# design.net
KiCad netlist of a schematic drawn in Altium Designer
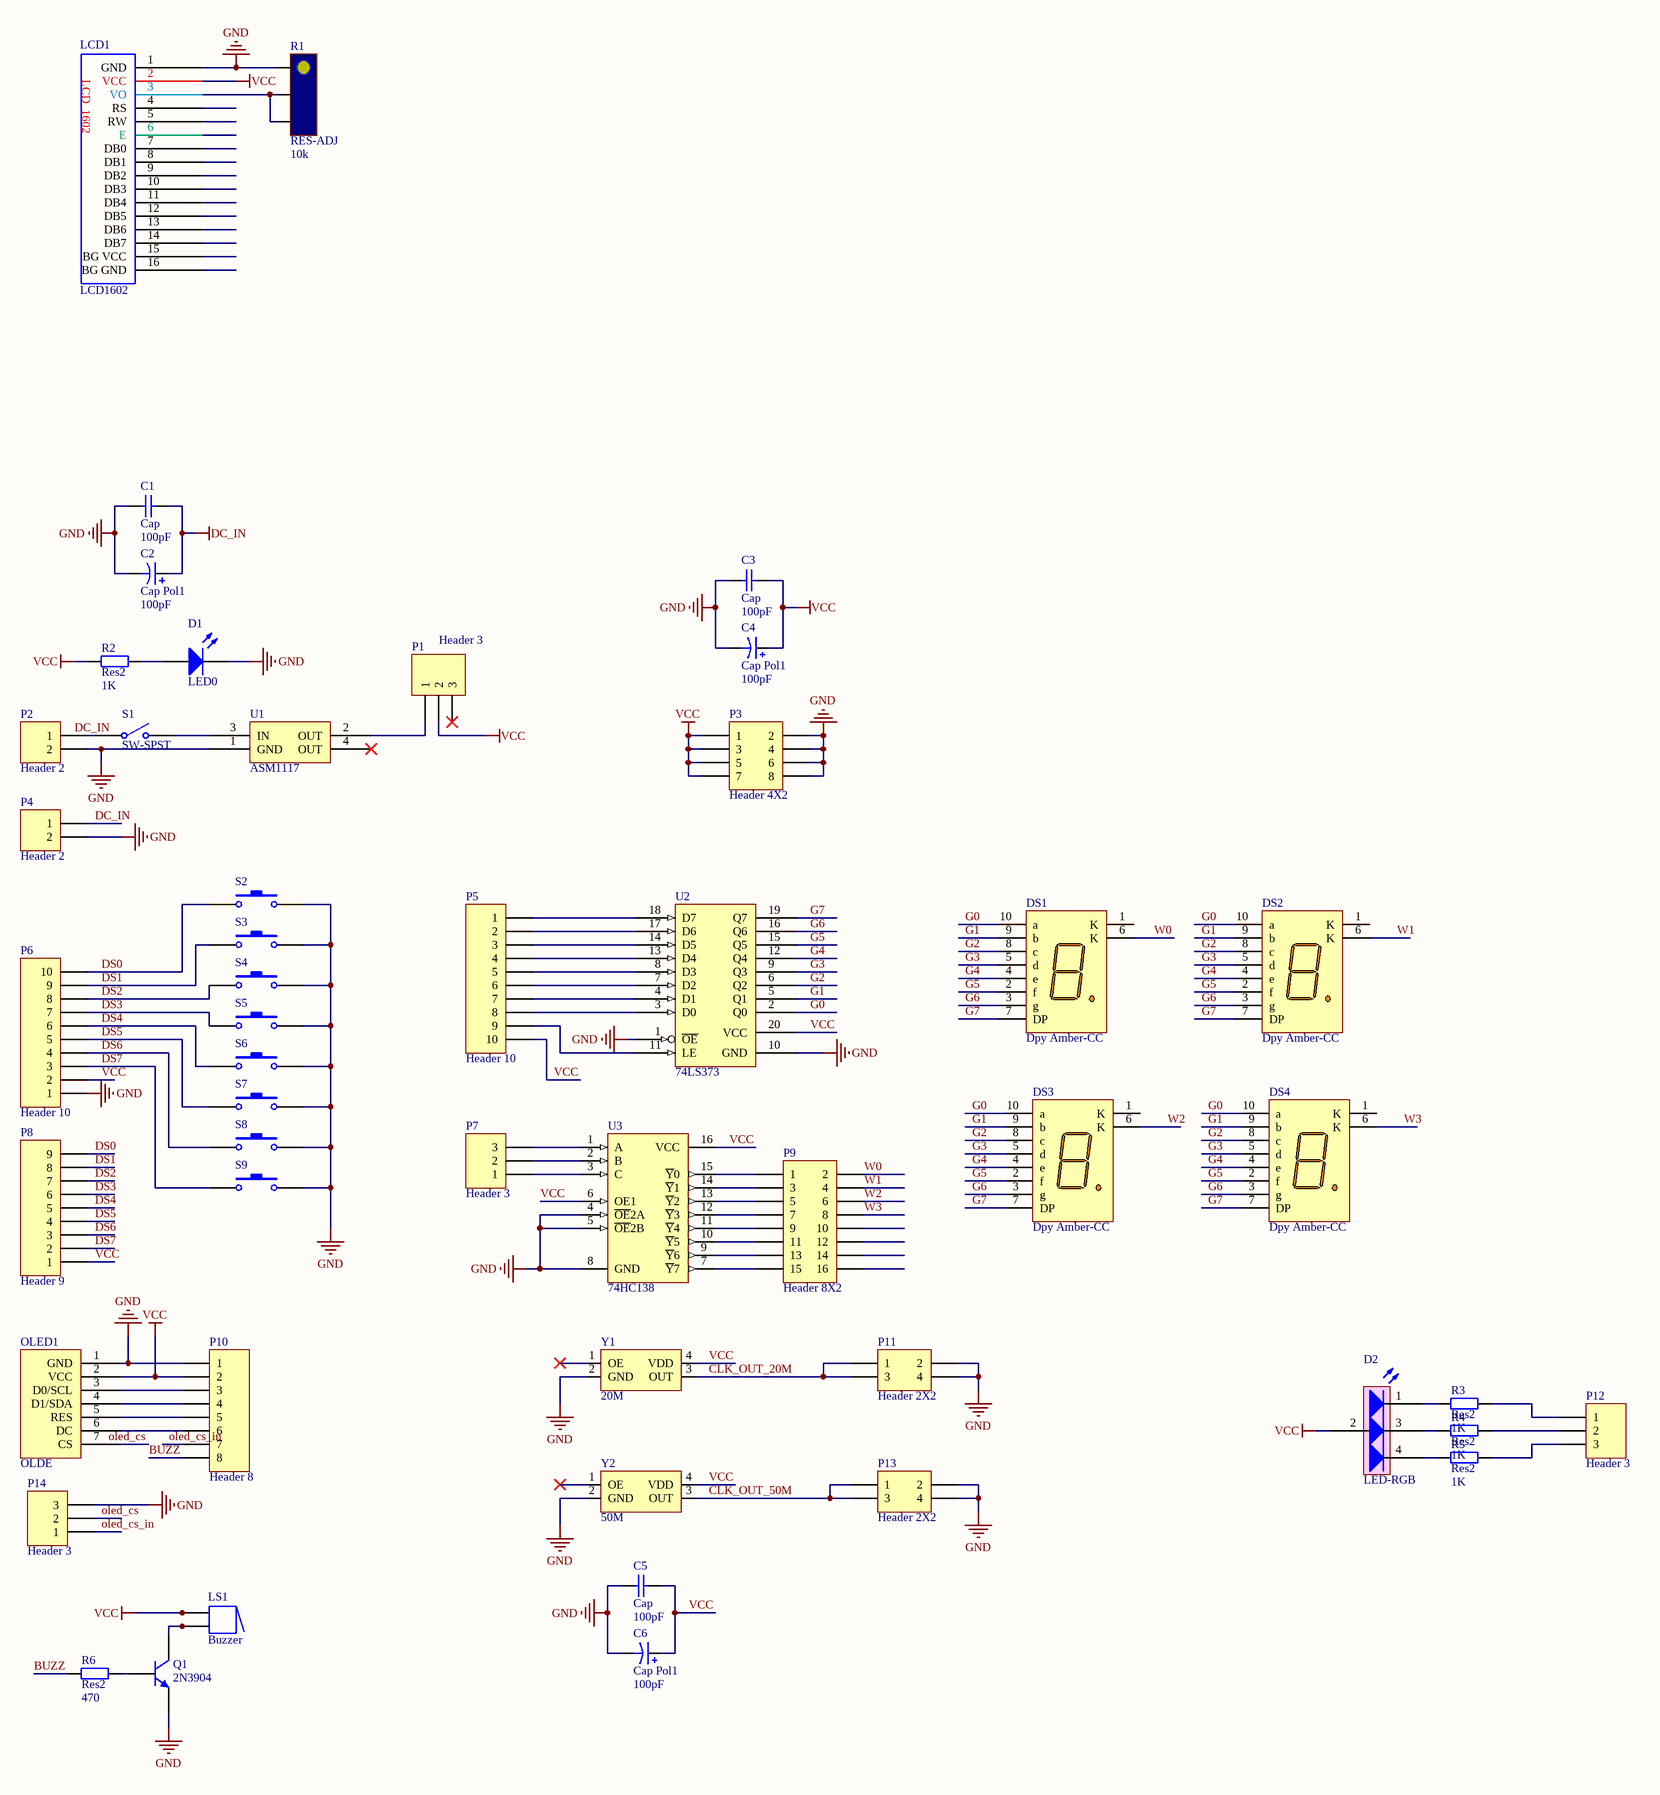
[diagram p0: 按键_数码管.SchDoc]

(export (version "E")
  (design (tool "Eeschema 10.0.6"))
  (components
    (comp (ref "C1")
      (value "Cap")
      (footprint "C-0805")
      (description "Capacitor")
      (fields (field (name "ALTIUM_VALUE") "100pF") (field (name "PUBLISHER") "Altium Limited"))
      (libsource (lib "Miscellaneous Devices") (part "Cap"))
    )
    (comp (ref "C2")
      (value "Cap Pol1")
      (footprint "C-RB-8")
      (description "Polarized Capacitor (Radial)")
      (fields (field (name "ALTIUM_VALUE") "100pF") (field (name "PUBLISHER") "Altium Limited"))
      (libsource (lib "Miscellaneous Devices") (part "Cap Pol1"))
    )
    (comp (ref "C3")
      (value "Cap")
      (footprint "C-0805")
      (description "Capacitor")
      (fields (field (name "ALTIUM_VALUE") "100pF") (field (name "PUBLISHER") "Altium Limited"))
      (libsource (lib "Miscellaneous Devices") (part "Cap"))
    )
    (comp (ref "C4")
      (value "Cap Pol1")
      (footprint "C-RB-8")
      (description "Polarized Capacitor (Radial)")
      (fields (field (name "ALTIUM_VALUE") "100pF") (field (name "PUBLISHER") "Altium Limited"))
      (libsource (lib "Miscellaneous Devices") (part "Cap Pol1"))
    )
    (comp (ref "C5")
      (value "Cap")
      (footprint "C-0805")
      (description "Capacitor")
      (fields (field (name "ALTIUM_VALUE") "100pF") (field (name "PUBLISHER") "Altium Limited"))
      (libsource (lib "Miscellaneous Devices") (part "Cap"))
    )
    (comp (ref "C6")
      (value "Cap Pol1")
      (footprint "C-RB-8")
      (description "Polarized Capacitor (Radial)")
      (fields (field (name "ALTIUM_VALUE") "100pF") (field (name "PUBLISHER") "Altium Limited"))
      (libsource (lib "Miscellaneous Devices") (part "Cap Pol1"))
    )
    (comp (ref "D1")
      (value "LED0")
      (footprint "LED")
      (description "Typical INFRARED GaAs LED")
      (fields (field (name "PUBLISHER") "Altium Limited"))
      (libsource (lib "Miscellaneous Devices") (part "LED0"))
    )
    (comp (ref "D2")
      (value "LED-RGB")
      (footprint "LED-RGB")
      (description "三基色LED")
      (fields (field (name "PUBLISHER") "Altium Limited"))
      (libsource (lib "常用封装") (part "LED-RGB"))
    )
    (comp (ref "DS1")
      (value "Dpy Amber-CC")
      (footprint "A")
      (description "7.62 mm Black Surface Orange 7-Segment Display: CC, RH DP")
      (fields (field (name "PUBLISHER") "Altium Limited"))
      (libsource (lib "Miscellaneous Devices") (part "Dpy Amber-CC"))
    )
    (comp (ref "DS2")
      (value "Dpy Amber-CC")
      (footprint "A")
      (description "7.62 mm Black Surface Orange 7-Segment Display: CC, RH DP")
      (fields (field (name "PUBLISHER") "Altium Limited"))
      (libsource (lib "Miscellaneous Devices") (part "Dpy Amber-CC"))
    )
    (comp (ref "DS3")
      (value "Dpy Amber-CC")
      (footprint "A")
      (description "7.62 mm Black Surface Orange 7-Segment Display: CC, RH DP")
      (fields (field (name "PUBLISHER") "Altium Limited"))
      (libsource (lib "Miscellaneous Devices") (part "Dpy Amber-CC"))
    )
    (comp (ref "DS4")
      (value "Dpy Amber-CC")
      (footprint "A")
      (description "7.62 mm Black Surface Orange 7-Segment Display: CC, RH DP")
      (fields (field (name "PUBLISHER") "Altium Limited"))
      (libsource (lib "Miscellaneous Devices") (part "Dpy Amber-CC"))
    )
    (comp (ref "LCD1") (value "LCD1602") (footprint "1602LCD") (libsource (lib "常用封装") (part "LCD1602")))
    (comp (ref "LS1")
      (value "Buzzer")
      (footprint "Beep")
      (description "Magnetic Transducer Buzzer")
      (fields (field (name "PUBLISHER") "Altium Limited"))
      (libsource (lib "Miscellaneous Devices") (part "Buzzer"))
    )
    (comp (ref "OLED1") (value "OLDE") (footprint "HDR1X7") (libsource (lib "常用封装") (part "OLED-0.96寸")))
    (comp (ref "P1")
      (value "Header 3")
      (footprint "HDR1X3")
      (description "Header, 3-Pin")
      (fields (field (name "PUBLISHER") "Altium Limited"))
      (libsource (lib "") (part "Header 3_1"))
    )
    (comp (ref "P2")
      (value "Header 2")
      (footprint "USB_B1")
      (description "Header, 2-Pin")
      (fields (field (name "PUBLISHER") "Altium Limited"))
      (libsource (lib "Miscellaneous Connectors") (part "Header 2"))
    )
    (comp (ref "P3")
      (value "Header 4X2")
      (footprint "HDR2X4")
      (description "Header, 4-Pin, Dual row")
      (fields (field (name "PUBLISHER") "Altium Limited"))
      (libsource (lib "Miscellaneous Connectors") (part "Header 4X2"))
    )
    (comp (ref "P4")
      (value "Header 2")
      (footprint "USB_B1")
      (description "Header, 2-Pin")
      (fields (field (name "PUBLISHER") "Altium Limited"))
      (libsource (lib "Miscellaneous Connectors") (part "Header 2"))
    )
    (comp (ref "P5")
      (value "Header 10")
      (footprint "HDR1X10")
      (description "Header, 10-Pin")
      (fields (field (name "PUBLISHER") "Altium Limited"))
      (libsource (lib "") (part "Header 10_1"))
    )
    (comp (ref "P6")
      (value "Header 10")
      (footprint "HDR1X10")
      (description "Header, 10-Pin")
      (fields (field (name "PUBLISHER") "Altium Limited"))
      (libsource (lib "Miscellaneous Connectors") (part "Header 10"))
    )
    (comp (ref "P7")
      (value "Header 3")
      (footprint "HDR1X3")
      (description "Header, 3-Pin")
      (fields (field (name "PUBLISHER") "Altium Limited"))
      (libsource (lib "") (part "Header 3_2"))
    )
    (comp (ref "P8")
      (value "Header 9")
      (footprint "HDR1X9")
      (description "Header, 9-Pin")
      (fields (field (name "PUBLISHER") "Altium Limited"))
      (libsource (lib "Miscellaneous Connectors") (part "Header 9"))
    )
    (comp (ref "P9")
      (value "Header 8X2")
      (footprint "HDR2X8")
      (description "Header, 8-Pin, Dual row")
      (fields (field (name "PUBLISHER") "Altium Limited"))
      (libsource (lib "Miscellaneous Connectors") (part "Header 8X2"))
    )
    (comp (ref "P10")
      (value "Header 8")
      (footprint "HDR1X8")
      (description "Header, 8-Pin")
      (fields (field (name "PUBLISHER") "Altium Limited"))
      (libsource (lib "Miscellaneous Connectors") (part "Header 8"))
    )
    (comp (ref "P11")
      (value "Header 2X2")
      (footprint "HDR2X2")
      (description "Header, 2-Pin, Dual row")
      (fields (field (name "PUBLISHER") "Altium Limited"))
      (libsource (lib "Miscellaneous Connectors") (part "Header 2X2"))
    )
    (comp (ref "P12")
      (value "Header 3")
      (footprint "HDR1X3")
      (description "Header, 3-Pin")
      (fields (field (name "PUBLISHER") "Altium Limited"))
      (libsource (lib "Miscellaneous Connectors") (part "Header 3"))
    )
    (comp (ref "P13")
      (value "Header 2X2")
      (footprint "HDR2X2")
      (description "Header, 2-Pin, Dual row")
      (fields (field (name "PUBLISHER") "Altium Limited"))
      (libsource (lib "Miscellaneous Connectors") (part "Header 2X2"))
    )
    (comp (ref "P14")
      (value "Header 3")
      (footprint "HDR1X3")
      (description "Header, 3-Pin")
      (fields (field (name "PUBLISHER") "Altium Limited"))
      (libsource (lib "") (part "Header 3_2"))
    )
    (comp (ref "Q1")
      (value "2N3904")
      (footprint "SOT-23")
      (description "NPN General Purpose Amplifier")
      (fields (field (name "PUBLISHER") "Altium Limited"))
      (libsource (lib "Miscellaneous Devices") (part "2N3904"))
    )
    (comp (ref "R1")
      (value "RES-ADJ")
      (fields (field (name "ALTIUM_VALUE") "10k"))
      (libsource (lib "常用封装") (part "RES-ADJ"))
    )
    (comp (ref "R2")
      (value "Res2")
      (footprint "0805")
      (description "Resistor")
      (fields (field (name "ALTIUM_VALUE") "1K") (field (name "PUBLISHER") "Altium Limited"))
      (libsource (lib "Miscellaneous Devices") (part "Res2"))
    )
    (comp (ref "R3")
      (value "Res2")
      (footprint "0805")
      (description "Resistor")
      (fields (field (name "ALTIUM_VALUE") "1K") (field (name "PUBLISHER") "Altium Limited"))
      (libsource (lib "Miscellaneous Devices") (part "Res2"))
    )
    (comp (ref "R4")
      (value "Res2")
      (footprint "0805")
      (description "Resistor")
      (fields (field (name "ALTIUM_VALUE") "1K") (field (name "PUBLISHER") "Altium Limited"))
      (libsource (lib "Miscellaneous Devices") (part "Res2"))
    )
    (comp (ref "R5")
      (value "Res2")
      (footprint "0805")
      (description "Resistor")
      (fields (field (name "ALTIUM_VALUE") "1K") (field (name "PUBLISHER") "Altium Limited"))
      (libsource (lib "Miscellaneous Devices") (part "Res2"))
    )
    (comp (ref "R6")
      (value "Res2")
      (footprint "0805")
      (description "Resistor")
      (fields (field (name "ALTIUM_VALUE") "470") (field (name "PUBLISHER") "Altium Limited"))
      (libsource (lib "Miscellaneous Devices") (part "Res2"))
    )
    (comp (ref "S1")
      (value "SW-SPST")
      (footprint "SW-6pin")
      (description "Single-Pole, Single-Throw Switch")
      (fields (field (name "PUBLISHER") "Altium Limited"))
      (libsource (lib "Miscellaneous Devices") (part "SW-SPST"))
    )
    (comp (ref "S2")
      (value "SW-PB")
      (footprint "KeyA")
      (description "Switch")
      (fields (field (name "PUBLISHER") "Altium Limited"))
      (libsource (lib "Miscellaneous Devices") (part "SW-PB"))
    )
    (comp (ref "S3")
      (value "SW-PB")
      (footprint "KeyA")
      (description "Switch")
      (fields (field (name "PUBLISHER") "Altium Limited"))
      (libsource (lib "Miscellaneous Devices") (part "SW-PB"))
    )
    (comp (ref "S4")
      (value "SW-PB")
      (footprint "KeyA")
      (description "Switch")
      (fields (field (name "PUBLISHER") "Altium Limited"))
      (libsource (lib "Miscellaneous Devices") (part "SW-PB"))
    )
    (comp (ref "S5")
      (value "SW-PB")
      (footprint "KeyA")
      (description "Switch")
      (fields (field (name "PUBLISHER") "Altium Limited"))
      (libsource (lib "Miscellaneous Devices") (part "SW-PB"))
    )
    (comp (ref "S6")
      (value "SW-PB")
      (footprint "KeyA")
      (description "Switch")
      (fields (field (name "PUBLISHER") "Altium Limited"))
      (libsource (lib "Miscellaneous Devices") (part "SW-PB"))
    )
    (comp (ref "S7")
      (value "SW-PB")
      (footprint "KeyA")
      (description "Switch")
      (fields (field (name "PUBLISHER") "Altium Limited"))
      (libsource (lib "Miscellaneous Devices") (part "SW-PB"))
    )
    (comp (ref "S8")
      (value "SW-PB")
      (footprint "KeyA")
      (description "Switch")
      (fields (field (name "PUBLISHER") "Altium Limited"))
      (libsource (lib "Miscellaneous Devices") (part "SW-PB"))
    )
    (comp (ref "S9")
      (value "SW-PB")
      (footprint "KeyA")
      (description "Switch")
      (fields (field (name "PUBLISHER") "Altium Limited"))
      (libsource (lib "Miscellaneous Devices") (part "SW-PB"))
    )
    (comp (ref "U1")
      (value "ASM1117")
      (footprint "SOT-223")
      (description "3.3V稳压芯片")
      (libsource (lib "常用封装") (part "ASM1117"))
    )
    (comp (ref "U2") (value "74LS373") (footprint "DIP20") (libsource (lib "常用封装") (part "74LS373")))
    (comp (ref "U3")
      (value "74HC138")
      (footprint "DIP16")
      (description "138译码器")
      (fields (field (name "PUBLISHER") "Altium Limited"))
      (libsource (lib "常用封装") (part "74HC138"))
    )
    (comp (ref "Y1")
      (value "20M")
      (footprint "XTAL-OCX7050 - M")
      (description "贴片有源晶振")
      (fields (field (name "Comment") "XATLS"))
      (libsource (lib "常用封装") (part "XATLS"))
    )
    (comp (ref "Y2")
      (value "50M")
      (footprint "XTAL-OCX7050 - M")
      (description "贴片有源晶振")
      (fields (field (name "Comment") "XATLS"))
      (libsource (lib "常用封装") (part "XATLS"))
    )
  )
  (nets
    (net (code "1") (name "/BUZZ") (class "Default")
      (node (ref "P10") (pin "8") (pinfunction "8_8") (pintype "passive"))
      (node (ref "R6") (pin "1") (pinfunction "1_1") (pintype "passive"))
    )
    (net (code "2") (name "/CLK_OUT_20M") (class "Default")
      (node (ref "P11") (pin "1") (pinfunction "1_1") (pintype "passive"))
      (node (ref "P11") (pin "3") (pinfunction "3_3") (pintype "passive"))
      (node (ref "Y1") (pin "3") (pinfunction "OUT_3") (pintype "passive"))
    )
    (net (code "3") (name "/CLK_OUT_50M") (class "Default")
      (node (ref "P13") (pin "1") (pinfunction "1_1") (pintype "passive"))
      (node (ref "P13") (pin "3") (pinfunction "3_3") (pintype "passive"))
      (node (ref "Y2") (pin "3") (pinfunction "OUT_3") (pintype "passive"))
    )
    (net (code "4") (name "/DS0") (class "Default")
      (node (ref "P6") (pin "10") (pinfunction "10_10") (pintype "passive"))
      (node (ref "P8") (pin "9") (pinfunction "9_9") (pintype "passive"))
      (node (ref "S2") (pin "1") (pinfunction "1_1") (pintype "passive"))
    )
    (net (code "5") (name "/DS1") (class "Default")
      (node (ref "P6") (pin "9") (pinfunction "9_9") (pintype "passive"))
      (node (ref "P8") (pin "8") (pinfunction "8_8") (pintype "passive"))
      (node (ref "S3") (pin "1") (pinfunction "1_1") (pintype "passive"))
    )
    (net (code "6") (name "/DS2") (class "Default")
      (node (ref "P6") (pin "8") (pinfunction "8_8") (pintype "passive"))
      (node (ref "P8") (pin "7") (pinfunction "7_7") (pintype "passive"))
      (node (ref "S4") (pin "1") (pinfunction "1_1") (pintype "passive"))
    )
    (net (code "7") (name "/DS3") (class "Default")
      (node (ref "P6") (pin "7") (pinfunction "7_7") (pintype "passive"))
      (node (ref "P8") (pin "6") (pinfunction "6_6") (pintype "passive"))
      (node (ref "S5") (pin "1") (pinfunction "1_1") (pintype "passive"))
    )
    (net (code "8") (name "/DS4") (class "Default")
      (node (ref "P6") (pin "6") (pinfunction "6_6") (pintype "passive"))
      (node (ref "P8") (pin "5") (pinfunction "5_5") (pintype "passive"))
      (node (ref "S6") (pin "1") (pinfunction "1_1") (pintype "passive"))
    )
    (net (code "9") (name "/DS5") (class "Default")
      (node (ref "P6") (pin "5") (pinfunction "5_5") (pintype "passive"))
      (node (ref "P8") (pin "4") (pinfunction "4_4") (pintype "passive"))
      (node (ref "S7") (pin "1") (pinfunction "1_1") (pintype "passive"))
    )
    (net (code "10") (name "/DS6") (class "Default")
      (node (ref "P6") (pin "4") (pinfunction "4_4") (pintype "passive"))
      (node (ref "P8") (pin "3") (pinfunction "3_3") (pintype "passive"))
      (node (ref "S8") (pin "1") (pinfunction "1_1") (pintype "passive"))
    )
    (net (code "11") (name "/DS7") (class "Default")
      (node (ref "P6") (pin "3") (pinfunction "3_3") (pintype "passive"))
      (node (ref "P8") (pin "2") (pinfunction "2_2") (pintype "passive"))
      (node (ref "S9") (pin "1") (pinfunction "1_1") (pintype "passive"))
    )
    (net (code "12") (name "/G0") (class "Default")
      (node (ref "DS1") (pin "10") (pinfunction "a_10") (pintype "passive"))
      (node (ref "DS2") (pin "10") (pinfunction "a_10") (pintype "passive"))
      (node (ref "DS3") (pin "10") (pinfunction "a_10") (pintype "passive"))
      (node (ref "DS4") (pin "10") (pinfunction "a_10") (pintype "passive"))
      (node (ref "U2") (pin "2") (pinfunction "Q0_2") (pintype "tri_state"))
    )
    (net (code "13") (name "/G1") (class "Default")
      (node (ref "DS1") (pin "9") (pinfunction "b_9") (pintype "passive"))
      (node (ref "DS2") (pin "9") (pinfunction "b_9") (pintype "passive"))
      (node (ref "DS3") (pin "9") (pinfunction "b_9") (pintype "passive"))
      (node (ref "DS4") (pin "9") (pinfunction "b_9") (pintype "passive"))
      (node (ref "U2") (pin "5") (pinfunction "Q1_5") (pintype "tri_state"))
    )
    (net (code "14") (name "/G2") (class "Default")
      (node (ref "DS1") (pin "8") (pinfunction "c_8") (pintype "passive"))
      (node (ref "DS2") (pin "8") (pinfunction "c_8") (pintype "passive"))
      (node (ref "DS3") (pin "8") (pinfunction "c_8") (pintype "passive"))
      (node (ref "DS4") (pin "8") (pinfunction "c_8") (pintype "passive"))
      (node (ref "U2") (pin "6") (pinfunction "Q2_6") (pintype "tri_state"))
    )
    (net (code "15") (name "/G3") (class "Default")
      (node (ref "DS1") (pin "5") (pinfunction "d_5") (pintype "passive"))
      (node (ref "DS2") (pin "5") (pinfunction "d_5") (pintype "passive"))
      (node (ref "DS3") (pin "5") (pinfunction "d_5") (pintype "passive"))
      (node (ref "DS4") (pin "5") (pinfunction "d_5") (pintype "passive"))
      (node (ref "U2") (pin "9") (pinfunction "Q3_9") (pintype "tri_state"))
    )
    (net (code "16") (name "/G4") (class "Default")
      (node (ref "DS1") (pin "4") (pinfunction "e_4") (pintype "passive"))
      (node (ref "DS2") (pin "4") (pinfunction "e_4") (pintype "passive"))
      (node (ref "DS3") (pin "4") (pinfunction "e_4") (pintype "passive"))
      (node (ref "DS4") (pin "4") (pinfunction "e_4") (pintype "passive"))
      (node (ref "U2") (pin "12") (pinfunction "Q4_12") (pintype "tri_state"))
    )
    (net (code "17") (name "/G5") (class "Default")
      (node (ref "DS1") (pin "2") (pinfunction "f_2") (pintype "passive"))
      (node (ref "DS2") (pin "2") (pinfunction "f_2") (pintype "passive"))
      (node (ref "DS3") (pin "2") (pinfunction "f_2") (pintype "passive"))
      (node (ref "DS4") (pin "2") (pinfunction "f_2") (pintype "passive"))
      (node (ref "U2") (pin "15") (pinfunction "Q5_15") (pintype "tri_state"))
    )
    (net (code "18") (name "/G6") (class "Default")
      (node (ref "DS1") (pin "3") (pinfunction "g_3") (pintype "passive"))
      (node (ref "DS2") (pin "3") (pinfunction "g_3") (pintype "passive"))
      (node (ref "DS3") (pin "3") (pinfunction "g_3") (pintype "passive"))
      (node (ref "DS4") (pin "3") (pinfunction "g_3") (pintype "passive"))
      (node (ref "U2") (pin "16") (pinfunction "Q6_16") (pintype "tri_state"))
    )
    (net (code "19") (name "/G7") (class "Default")
      (node (ref "DS1") (pin "7") (pinfunction "DP_7") (pintype "passive"))
      (node (ref "DS2") (pin "7") (pinfunction "DP_7") (pintype "passive"))
      (node (ref "DS3") (pin "7") (pinfunction "DP_7") (pintype "passive"))
      (node (ref "DS4") (pin "7") (pinfunction "DP_7") (pintype "passive"))
      (node (ref "U2") (pin "19") (pinfunction "Q7_19") (pintype "tri_state"))
    )
    (net (code "20") (name "/W0") (class "Default")
      (node (ref "DS1") (pin "6") (pinfunction "K_6") (pintype "passive"))
      (node (ref "P9") (pin "2") (pinfunction "2_2") (pintype "passive"))
    )
    (net (code "21") (name "/W1") (class "Default")
      (node (ref "DS2") (pin "6") (pinfunction "K_6") (pintype "passive"))
      (node (ref "P9") (pin "4") (pinfunction "4_4") (pintype "passive"))
    )
    (net (code "22") (name "/W2") (class "Default")
      (node (ref "DS3") (pin "6") (pinfunction "K_6") (pintype "passive"))
      (node (ref "P9") (pin "6") (pinfunction "6_6") (pintype "passive"))
    )
    (net (code "23") (name "/W3") (class "Default")
      (node (ref "DS4") (pin "6") (pinfunction "K_6") (pintype "passive"))
      (node (ref "P9") (pin "8") (pinfunction "8_8") (pintype "passive"))
    )
    (net (code "24") (name "/oled_cs") (class "Default")
      (node (ref "P14") (pin "2") (pinfunction "2_2") (pintype "passive"))
    )
    (net (code "25") (name "/oled_cs_in") (class "Default")
      (node (ref "P10") (pin "7") (pinfunction "7_7") (pintype "passive"))
      (node (ref "P14") (pin "1") (pinfunction "1_1") (pintype "passive"))
    )
    (net (code "26") (name "DC_IN") (class "Default")
      (node (ref "C1") (pin "2") (pinfunction "2_2") (pintype "passive"))
      (node (ref "C2") (pin "1") (pinfunction "1_1") (pintype "passive"))
      (node (ref "P4") (pin "1") (pinfunction "1_1") (pintype "passive"))
    )
    (net (code "27") (name "GND") (class "Default")
      (node (ref "C1") (pin "1") (pinfunction "1_1") (pintype "passive"))
      (node (ref "C2") (pin "2") (pinfunction "2_2") (pintype "passive"))
      (node (ref "C3") (pin "1") (pinfunction "1_1") (pintype "passive"))
      (node (ref "C4") (pin "2") (pinfunction "2_2") (pintype "passive"))
      (node (ref "C5") (pin "1") (pinfunction "1_1") (pintype "passive"))
      (node (ref "C6") (pin "2") (pinfunction "2_2") (pintype "passive"))
      (node (ref "D1") (pin "2") (pinfunction "K_2") (pintype "passive"))
      (node (ref "LCD1") (pin "1") (pinfunction "GND_1") (pintype "passive"))
      (node (ref "OLED1") (pin "1") (pinfunction "GND_1") (pintype "passive"))
      (node (ref "P10") (pin "1") (pinfunction "1_1") (pintype "passive"))
      (node (ref "P11") (pin "2") (pinfunction "2_2") (pintype "passive"))
      (node (ref "P11") (pin "4") (pinfunction "4_4") (pintype "passive"))
      (node (ref "P13") (pin "2") (pinfunction "2_2") (pintype "passive"))
      (node (ref "P13") (pin "4") (pinfunction "4_4") (pintype "passive"))
      (node (ref "P14") (pin "3") (pinfunction "3_3") (pintype "passive"))
      (node (ref "P2") (pin "2") (pinfunction "2_2") (pintype "passive"))
      (node (ref "P3") (pin "2") (pinfunction "2_2") (pintype "passive"))
      (node (ref "P3") (pin "4") (pinfunction "4_4") (pintype "passive"))
      (node (ref "P3") (pin "6") (pinfunction "6_6") (pintype "passive"))
      (node (ref "P3") (pin "8") (pinfunction "8_8") (pintype "passive"))
      (node (ref "P4") (pin "2") (pinfunction "2_2") (pintype "passive"))
      (node (ref "P6") (pin "1") (pinfunction "1_1") (pintype "passive"))
      (node (ref "Q1") (pin "1") (pinfunction "E_1") (pintype "passive"))
      (node (ref "R1") (pin "3") (pinfunction "3_3") (pintype "passive"))
      (node (ref "S2") (pin "2") (pinfunction "2_2") (pintype "passive"))
      (node (ref "S3") (pin "2") (pinfunction "2_2") (pintype "passive"))
      (node (ref "S4") (pin "2") (pinfunction "2_2") (pintype "passive"))
      (node (ref "S5") (pin "2") (pinfunction "2_2") (pintype "passive"))
      (node (ref "S6") (pin "2") (pinfunction "2_2") (pintype "passive"))
      (node (ref "S7") (pin "2") (pinfunction "2_2") (pintype "passive"))
      (node (ref "S8") (pin "2") (pinfunction "2_2") (pintype "passive"))
      (node (ref "S9") (pin "2") (pinfunction "2_2") (pintype "passive"))
      (node (ref "U1") (pin "1") (pinfunction "GND_1") (pintype "passive"))
      (node (ref "U2") (pin "1") (pinfunction "~{OE}_1") (pintype "input"))
      (node (ref "U2") (pin "10") (pinfunction "GND_10") (pintype "power_in"))
      (node (ref "U3") (pin "4") (pinfunction "~{OE}2A_4") (pintype "input"))
      (node (ref "U3") (pin "5") (pinfunction "~{OE}2B_5") (pintype "input"))
      (node (ref "U3") (pin "8") (pinfunction "GND_8") (pintype "power_in"))
      (node (ref "Y1") (pin "2") (pinfunction "GND_2") (pintype "passive"))
      (node (ref "Y2") (pin "2") (pinfunction "GND_2") (pintype "passive"))
    )
    (net (code "28") (name "Net-(D1-A)") (class "Default")
      (node (ref "D1") (pin "1") (pinfunction "A_1") (pintype "passive"))
      (node (ref "R2") (pin "2") (pinfunction "2_2") (pintype "passive"))
    )
    (net (code "29") (name "Net-(D2-B)") (class "Default")
      (node (ref "D2") (pin "4") (pinfunction "B_4") (pintype "passive"))
      (node (ref "R5") (pin "1") (pinfunction "1_1") (pintype "passive"))
    )
    (net (code "30") (name "Net-(D2-G)") (class "Default")
      (node (ref "D2") (pin "3") (pinfunction "G_3") (pintype "passive"))
      (node (ref "R4") (pin "1") (pinfunction "1_1") (pintype "passive"))
    )
    (net (code "31") (name "Net-(D2-R)") (class "Default")
      (node (ref "D2") (pin "1") (pinfunction "R_1") (pintype "passive"))
      (node (ref "R3") (pin "1") (pinfunction "1_1") (pintype "passive"))
    )
    (net (code "32") (name "Net-(LCD1-VO)") (class "Default")
      (node (ref "LCD1") (pin "3") (pinfunction "VO_3") (pintype "passive"))
      (node (ref "R1") (pin "1") (pinfunction "1_1") (pintype "passive"))
      (node (ref "R1") (pin "2") (pinfunction "2_2") (pintype "passive"))
    )
    (net (code "33") (name "Net-(OLED1-D0{slash}SCL)") (class "Default")
      (node (ref "OLED1") (pin "3") (pinfunction "D0/SCL_3") (pintype "passive"))
      (node (ref "P10") (pin "3") (pinfunction "3_3") (pintype "passive"))
    )
    (net (code "34") (name "Net-(OLED1-D1{slash}SDA)") (class "Default")
      (node (ref "OLED1") (pin "4") (pinfunction "D1/SDA_4") (pintype "passive"))
      (node (ref "P10") (pin "4") (pinfunction "4_4") (pintype "passive"))
    )
    (net (code "35") (name "Net-(OLED1-DC)") (class "Default")
      (node (ref "OLED1") (pin "6") (pinfunction "DC_6") (pintype "passive"))
      (node (ref "P10") (pin "6") (pinfunction "6_6") (pintype "passive"))
    )
    (net (code "36") (name "Net-(OLED1-RES)") (class "Default")
      (node (ref "OLED1") (pin "5") (pinfunction "RES_5") (pintype "passive"))
      (node (ref "P10") (pin "5") (pinfunction "5_5") (pintype "passive"))
    )
    (net (code "37") (name "Net-(P1-Pad1)") (class "Default")
      (node (ref "P1") (pin "1") (pinfunction "1_1") (pintype "passive"))
      (node (ref "U1") (pin "2") (pinfunction "OUT_2") (pintype "passive"))
    )
    (net (code "38") (name "Net-(P12-Pad1)") (class "Default")
      (node (ref "P12") (pin "1") (pinfunction "1_1") (pintype "passive"))
      (node (ref "R3") (pin "2") (pinfunction "2_2") (pintype "passive"))
    )
    (net (code "39") (name "Net-(P12-Pad2)") (class "Default")
      (node (ref "P12") (pin "2") (pinfunction "2_2") (pintype "passive"))
      (node (ref "R4") (pin "2") (pinfunction "2_2") (pintype "passive"))
    )
    (net (code "40") (name "Net-(P12-Pad3)") (class "Default")
      (node (ref "P12") (pin "3") (pinfunction "3_3") (pintype "passive"))
      (node (ref "R5") (pin "2") (pinfunction "2_2") (pintype "passive"))
    )
    (net (code "41") (name "Net-(Q1-B)") (class "Default")
      (node (ref "Q1") (pin "2") (pinfunction "B_2") (pintype "passive"))
      (node (ref "R6") (pin "2") (pinfunction "2_2") (pintype "passive"))
    )
    (net (code "42") (name "Net-(Q1-C)") (class "Default")
      (node (ref "LS1") (pin "2") (pinfunction "2_2") (pintype "passive"))
      (node (ref "LS1") (pin "2A") (pinfunction "2A_2A") (pintype "passive"))
      (node (ref "Q1") (pin "3") (pinfunction "C_3") (pintype "passive"))
    )
    (net (code "43") (name "Net-(S1-COMMON)") (class "Default")
      (node (ref "P2") (pin "1") (pinfunction "1_1") (pintype "passive"))
      (node (ref "S1") (pin "1") (pinfunction "COMMON_1") (pintype "passive"))
    )
    (net (code "44") (name "Net-(S1-NO)") (class "Default")
      (node (ref "S1") (pin "2") (pinfunction "NO_2") (pintype "passive"))
      (node (ref "U1") (pin "3") (pinfunction "IN_3") (pintype "passive"))
    )
    (net (code "45") (name "Net-(U2-D0)") (class "Default")
      (node (ref "P5") (pin "8") (pinfunction "8_8") (pintype "passive"))
      (node (ref "U2") (pin "3") (pinfunction "D0_3") (pintype "input"))
    )
    (net (code "46") (name "Net-(U2-D1)") (class "Default")
      (node (ref "P5") (pin "7") (pinfunction "7_7") (pintype "passive"))
      (node (ref "U2") (pin "4") (pinfunction "D1_4") (pintype "input"))
    )
    (net (code "47") (name "Net-(U2-D2)") (class "Default")
      (node (ref "P5") (pin "6") (pinfunction "6_6") (pintype "passive"))
      (node (ref "U2") (pin "7") (pinfunction "D2_7") (pintype "input"))
    )
    (net (code "48") (name "Net-(U2-D3)") (class "Default")
      (node (ref "P5") (pin "5") (pinfunction "5_5") (pintype "passive"))
      (node (ref "U2") (pin "8") (pinfunction "D3_8") (pintype "input"))
    )
    (net (code "49") (name "Net-(U2-D4)") (class "Default")
      (node (ref "P5") (pin "4") (pinfunction "4_4") (pintype "passive"))
      (node (ref "U2") (pin "13") (pinfunction "D4_13") (pintype "input"))
    )
    (net (code "50") (name "Net-(U2-D5)") (class "Default")
      (node (ref "P5") (pin "3") (pinfunction "3_3") (pintype "passive"))
      (node (ref "U2") (pin "14") (pinfunction "D5_14") (pintype "input"))
    )
    (net (code "51") (name "Net-(U2-D6)") (class "Default")
      (node (ref "P5") (pin "2") (pinfunction "2_2") (pintype "passive"))
      (node (ref "U2") (pin "17") (pinfunction "D6_17") (pintype "input"))
    )
    (net (code "52") (name "Net-(U2-D7)") (class "Default")
      (node (ref "P5") (pin "1") (pinfunction "1_1") (pintype "passive"))
      (node (ref "U2") (pin "18") (pinfunction "D7_18") (pintype "input"))
    )
    (net (code "53") (name "Net-(U2-LE)") (class "Default")
      (node (ref "P5") (pin "9") (pinfunction "9_9") (pintype "passive"))
      (node (ref "U2") (pin "11") (pinfunction "LE_11") (pintype "input"))
    )
    (net (code "54") (name "Net-(U3-A)") (class "Default")
      (node (ref "P7") (pin "3") (pinfunction "3_3") (pintype "passive"))
      (node (ref "U3") (pin "1") (pinfunction "A_1") (pintype "input"))
    )
    (net (code "55") (name "Net-(U3-B)") (class "Default")
      (node (ref "P7") (pin "2") (pinfunction "2_2") (pintype "passive"))
      (node (ref "U3") (pin "2") (pinfunction "B_2") (pintype "input"))
    )
    (net (code "56") (name "Net-(U3-C)") (class "Default")
      (node (ref "P7") (pin "1") (pinfunction "1_1") (pintype "passive"))
      (node (ref "U3") (pin "3") (pinfunction "C_3") (pintype "input"))
    )
    (net (code "57") (name "Net-(U3-~{Y}0)") (class "Default")
      (node (ref "P9") (pin "1") (pinfunction "1_1") (pintype "passive"))
      (node (ref "U3") (pin "15") (pinfunction "~{Y}0_15") (pintype "output"))
    )
    (net (code "58") (name "Net-(U3-~{Y}1)") (class "Default")
      (node (ref "P9") (pin "3") (pinfunction "3_3") (pintype "passive"))
      (node (ref "U3") (pin "14") (pinfunction "~{Y}1_14") (pintype "output"))
    )
    (net (code "59") (name "Net-(U3-~{Y}2)") (class "Default")
      (node (ref "P9") (pin "5") (pinfunction "5_5") (pintype "passive"))
      (node (ref "U3") (pin "13") (pinfunction "~{Y}2_13") (pintype "output"))
    )
    (net (code "60") (name "Net-(U3-~{Y}3)") (class "Default")
      (node (ref "P9") (pin "7") (pinfunction "7_7") (pintype "passive"))
      (node (ref "U3") (pin "12") (pinfunction "~{Y}3_12") (pintype "output"))
    )
    (net (code "61") (name "Net-(U3-~{Y}4)") (class "Default")
      (node (ref "P9") (pin "9") (pinfunction "9_9") (pintype "passive"))
      (node (ref "U3") (pin "11") (pinfunction "~{Y}4_11") (pintype "output"))
    )
    (net (code "62") (name "Net-(U3-~{Y}5)") (class "Default")
      (node (ref "P9") (pin "11") (pinfunction "11_11") (pintype "passive"))
      (node (ref "U3") (pin "10") (pinfunction "~{Y}5_10") (pintype "output"))
    )
    (net (code "63") (name "Net-(U3-~{Y}6)") (class "Default")
      (node (ref "P9") (pin "13") (pinfunction "13_13") (pintype "passive"))
      (node (ref "U3") (pin "9") (pinfunction "~{Y}6_9") (pintype "output"))
    )
    (net (code "64") (name "Net-(U3-~{Y}7)") (class "Default")
      (node (ref "P9") (pin "15") (pinfunction "15_15") (pintype "passive"))
      (node (ref "U3") (pin "7") (pinfunction "~{Y}7_7") (pintype "output"))
    )
    (net (code "65") (name "VCC") (class "Default")
      (node (ref "C3") (pin "2") (pinfunction "2_2") (pintype "passive"))
      (node (ref "C4") (pin "1") (pinfunction "1_1") (pintype "passive"))
      (node (ref "C5") (pin "2") (pinfunction "2_2") (pintype "passive"))
      (node (ref "C6") (pin "1") (pinfunction "1_1") (pintype "passive"))
      (node (ref "D2") (pin "2") (pinfunction "A_2") (pintype "passive"))
      (node (ref "LCD1") (pin "2") (pinfunction "VCC_2") (pintype "passive"))
      (node (ref "LS1") (pin "1") (pinfunction "1_1") (pintype "passive"))
      (node (ref "LS1") (pin "1A") (pinfunction "1A_1A") (pintype "passive"))
      (node (ref "OLED1") (pin "2") (pinfunction "VCC_2") (pintype "passive"))
      (node (ref "P1") (pin "2") (pinfunction "2_2") (pintype "passive"))
      (node (ref "P10") (pin "2") (pinfunction "2_2") (pintype "passive"))
      (node (ref "P3") (pin "1") (pinfunction "1_1") (pintype "passive"))
      (node (ref "P3") (pin "3") (pinfunction "3_3") (pintype "passive"))
      (node (ref "P3") (pin "5") (pinfunction "5_5") (pintype "passive"))
      (node (ref "P3") (pin "7") (pinfunction "7_7") (pintype "passive"))
      (node (ref "P5") (pin "10") (pinfunction "10_10") (pintype "passive"))
      (node (ref "P6") (pin "2") (pinfunction "2_2") (pintype "passive"))
      (node (ref "P8") (pin "1") (pinfunction "1_1") (pintype "passive"))
      (node (ref "R2") (pin "1") (pinfunction "1_1") (pintype "passive"))
      (node (ref "U2") (pin "20") (pinfunction "VCC_20") (pintype "power_in"))
      (node (ref "U3") (pin "16") (pinfunction "VCC_16") (pintype "power_in"))
      (node (ref "U3") (pin "6") (pinfunction "OE1_6") (pintype "input"))
      (node (ref "Y1") (pin "4") (pinfunction "VDD_4") (pintype "passive"))
      (node (ref "Y2") (pin "4") (pinfunction "VDD_4") (pintype "passive"))
    )
    (net (code "66") (name "unconnected-(DS1-K-Pad1)") (class "Default")
      (node (ref "DS1") (pin "1") (pinfunction "K_1") (pintype "passive"))
    )
    (net (code "67") (name "unconnected-(DS2-K-Pad1)") (class "Default")
      (node (ref "DS2") (pin "1") (pinfunction "K_1") (pintype "passive"))
    )
    (net (code "68") (name "unconnected-(DS3-K-Pad1)") (class "Default")
      (node (ref "DS3") (pin "1") (pinfunction "K_1") (pintype "passive"))
    )
    (net (code "69") (name "unconnected-(DS4-K-Pad1)") (class "Default")
      (node (ref "DS4") (pin "1") (pinfunction "K_1") (pintype "passive"))
    )
    (net (code "70") (name "unconnected-(LCD1-BG_GND-Pad16)") (class "Default")
      (node (ref "LCD1") (pin "16") (pinfunction "BG_GND_16") (pintype "passive"))
    )
    (net (code "71") (name "unconnected-(LCD1-BG_VCC-Pad15)") (class "Default")
      (node (ref "LCD1") (pin "15") (pinfunction "BG_VCC_15") (pintype "passive"))
    )
    (net (code "72") (name "unconnected-(LCD1-DB0-Pad7)") (class "Default")
      (node (ref "LCD1") (pin "7") (pinfunction "DB0_7") (pintype "passive"))
    )
    (net (code "73") (name "unconnected-(LCD1-DB1-Pad8)") (class "Default")
      (node (ref "LCD1") (pin "8") (pinfunction "DB1_8") (pintype "passive"))
    )
    (net (code "74") (name "unconnected-(LCD1-DB2-Pad9)") (class "Default")
      (node (ref "LCD1") (pin "9") (pinfunction "DB2_9") (pintype "passive"))
    )
    (net (code "75") (name "unconnected-(LCD1-DB3-Pad10)") (class "Default")
      (node (ref "LCD1") (pin "10") (pinfunction "DB3_10") (pintype "passive"))
    )
    (net (code "76") (name "unconnected-(LCD1-DB4-Pad11)") (class "Default")
      (node (ref "LCD1") (pin "11") (pinfunction "DB4_11") (pintype "passive"))
    )
    (net (code "77") (name "unconnected-(LCD1-DB5-Pad12)") (class "Default")
      (node (ref "LCD1") (pin "12") (pinfunction "DB5_12") (pintype "passive"))
    )
    (net (code "78") (name "unconnected-(LCD1-DB6-Pad13)") (class "Default")
      (node (ref "LCD1") (pin "13") (pinfunction "DB6_13") (pintype "passive"))
    )
    (net (code "79") (name "unconnected-(LCD1-DB7-Pad14)") (class "Default")
      (node (ref "LCD1") (pin "14") (pinfunction "DB7_14") (pintype "passive"))
    )
    (net (code "80") (name "unconnected-(LCD1-E-Pad6)") (class "Default")
      (node (ref "LCD1") (pin "6") (pinfunction "E_6") (pintype "passive"))
    )
    (net (code "81") (name "unconnected-(LCD1-RS-Pad4)") (class "Default")
      (node (ref "LCD1") (pin "4") (pinfunction "RS_4") (pintype "passive"))
    )
    (net (code "82") (name "unconnected-(LCD1-RW-Pad5)") (class "Default")
      (node (ref "LCD1") (pin "5") (pinfunction "RW_5") (pintype "passive"))
    )
    (net (code "83") (name "unconnected-(OLED1-CS-Pad7)") (class "Default")
      (node (ref "OLED1") (pin "7") (pinfunction "CS_7") (pintype "passive"))
    )
    (net (code "84") (name "unconnected-(P1-Pad3)") (class "Default")
      (node (ref "P1") (pin "3") (pinfunction "3_3") (pintype "passive+no_connect"))
    )
    (net (code "85") (name "unconnected-(P9-Pad10)") (class "Default")
      (node (ref "P9") (pin "10") (pinfunction "10_10") (pintype "passive"))
    )
    (net (code "86") (name "unconnected-(P9-Pad12)") (class "Default")
      (node (ref "P9") (pin "12") (pinfunction "12_12") (pintype "passive"))
    )
    (net (code "87") (name "unconnected-(P9-Pad14)") (class "Default")
      (node (ref "P9") (pin "14") (pinfunction "14_14") (pintype "passive"))
    )
    (net (code "88") (name "unconnected-(P9-Pad16)") (class "Default")
      (node (ref "P9") (pin "16") (pinfunction "16_16") (pintype "passive"))
    )
    (net (code "89") (name "unconnected-(U1-OUT-Pad4)") (class "Default")
      (node (ref "U1") (pin "4") (pinfunction "OUT_4") (pintype "passive+no_connect"))
    )
    (net (code "90") (name "unconnected-(Y1-OE-Pad1)") (class "Default")
      (node (ref "Y1") (pin "1") (pinfunction "OE_1") (pintype "passive+no_connect"))
    )
    (net (code "91") (name "unconnected-(Y2-OE-Pad1)") (class "Default")
      (node (ref "Y2") (pin "1") (pinfunction "OE_1") (pintype "passive+no_connect"))
    )
  )
)
